# motherboard.net
KiCad netlist of a schematic drawn in EAGLE
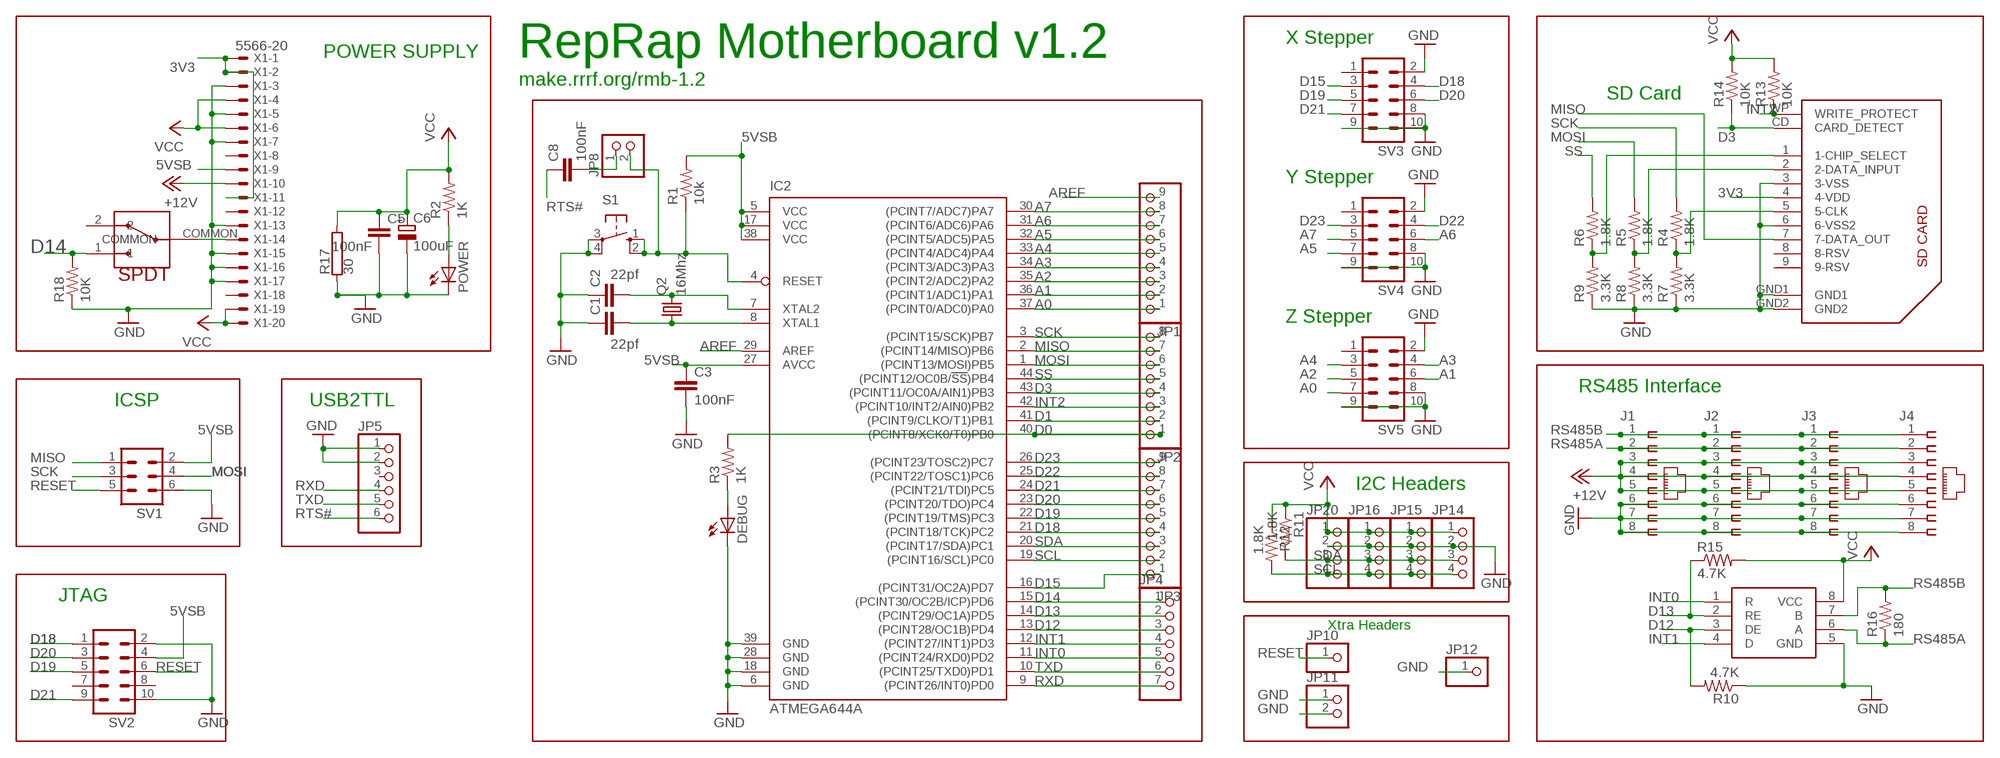
[diagram p0: schematic, sheet 1]

(export (version "E")
  (design (tool "Eeschema 10.0.6"))
  (components
    (comp (ref "C1")
      (value "22pf")
      (footprint "eagle-import:C1206")
      (libsource (lib "eagle-import") (part "C-EUC1206"))
    )
    (comp (ref "C2")
      (value "22pf")
      (footprint "eagle-import:C1206")
      (libsource (lib "eagle-import") (part "C-EUC1206"))
    )
    (comp (ref "C3")
      (value "100nF")
      (footprint "eagle-import:C1206")
      (libsource (lib "eagle-import") (part "C-EUC1206"))
    )
    (comp (ref "C5")
      (value "100nF")
      (footprint "eagle-import:C1206")
      (libsource (lib "eagle-import") (part "C-EUC1206"))
    )
    (comp (ref "C6")
      (value "100uF")
      (footprint "eagle-import:SANYO-OSCON_SMD_B6")
      (libsource (lib "eagle-import") (part "CPOL-EUSANYO_SMD_B6"))
    )
    (comp (ref "C8")
      (value "100nF")
      (footprint "eagle-import:C1206")
      (libsource (lib "eagle-import") (part "C-EUC1206"))
    )
    (comp (ref "DEBUG")
      (value "LEDCHIPLED_1206")
      (footprint "eagle-import:CHIPLED_1206")
      (libsource (lib "eagle-import") (part "LEDCHIPLED_1206"))
    )
    (comp (ref "IC1")
      (value "SN75176ASOIC")
      (footprint "eagle-import:SO08")
      (libsource (lib "eagle-import") (part "SN75176ASOIC"))
    )
    (comp (ref "IC2")
      (value "ATMEGA644A")
      (footprint "eagle-import:TQFP44")
      (libsource (lib "eagle-import") (part "ATMEGA644A"))
    )
    (comp (ref "J1")
      (value "555164-1")
      (footprint "eagle-import:555164-1")
      (libsource (lib "eagle-import") (part "555164-1"))
    )
    (comp (ref "J2")
      (value "555164-1")
      (footprint "eagle-import:555164-1")
      (libsource (lib "eagle-import") (part "555164-1"))
    )
    (comp (ref "J3")
      (value "555164-1")
      (footprint "eagle-import:555164-1")
      (libsource (lib "eagle-import") (part "555164-1"))
    )
    (comp (ref "J4")
      (value "555164-1")
      (footprint "eagle-import:555164-1")
      (libsource (lib "eagle-import") (part "555164-1"))
    )
    (comp (ref "JP1")
      (value "PINHD-1X9")
      (footprint "eagle-import:1X09")
      (libsource (lib "eagle-import") (part "PINHD-1X9"))
    )
    (comp (ref "JP2")
      (value "PINHD-1X8")
      (footprint "eagle-import:1X08")
      (libsource (lib "eagle-import") (part "PINHD-1X8"))
    )
    (comp (ref "JP3")
      (value "PINHD-1X9")
      (footprint "eagle-import:1X09")
      (libsource (lib "eagle-import") (part "PINHD-1X9"))
    )
    (comp (ref "JP4")
      (value "PINHD-1X7")
      (footprint "eagle-import:1X07")
      (libsource (lib "eagle-import") (part "PINHD-1X7"))
    )
    (comp (ref "JP5")
      (value "PINHD-1X6")
      (footprint "eagle-import:1X06")
      (libsource (lib "eagle-import") (part "PINHD-1X6"))
    )
    (comp (ref "JP8")
      (value "PINHD-1X2")
      (footprint "eagle-import:1X02")
      (libsource (lib "eagle-import") (part "PINHD-1X2"))
    )
    (comp (ref "JP10")
      (value "PINHD-1X1")
      (footprint "eagle-import:1X01")
      (libsource (lib "eagle-import") (part "PINHD-1X1"))
    )
    (comp (ref "JP11")
      (value "PINHD-1X2")
      (footprint "eagle-import:1X02")
      (libsource (lib "eagle-import") (part "PINHD-1X2"))
    )
    (comp (ref "JP12")
      (value "PINHD-1X1")
      (footprint "eagle-import:1X01")
      (libsource (lib "eagle-import") (part "PINHD-1X1"))
    )
    (comp (ref "JP14")
      (value "PINHD-1X4")
      (footprint "eagle-import:1X04")
      (libsource (lib "eagle-import") (part "PINHD-1X4"))
    )
    (comp (ref "JP15")
      (value "PINHD-1X4")
      (footprint "eagle-import:1X04")
      (libsource (lib "eagle-import") (part "PINHD-1X4"))
    )
    (comp (ref "JP16")
      (value "PINHD-1X4")
      (footprint "eagle-import:1X04")
      (libsource (lib "eagle-import") (part "PINHD-1X4"))
    )
    (comp (ref "JP20")
      (value "PINHD-1X4")
      (footprint "eagle-import:1X04")
      (libsource (lib "eagle-import") (part "PINHD-1X4"))
    )
    (comp (ref "POWER")
      (value "LEDCHIPLED_1206")
      (footprint "eagle-import:CHIPLED_1206")
      (libsource (lib "eagle-import") (part "LEDCHIPLED_1206"))
    )
    (comp (ref "Q2")
      (value "16Mhz")
      (footprint "eagle-import:HC49U-V")
      (libsource (lib "eagle-import") (part "CRYSTALHC49UV"))
    )
    (comp (ref "R1")
      (value "10k")
      (footprint "eagle-import:R1206")
      (libsource (lib "eagle-import") (part "R-US_R1206"))
    )
    (comp (ref "R2")
      (value "1K")
      (footprint "eagle-import:R1206")
      (libsource (lib "eagle-import") (part "R-US_R1206"))
    )
    (comp (ref "R3")
      (value "1K")
      (footprint "eagle-import:R1206")
      (libsource (lib "eagle-import") (part "resistor_R-US_R1206"))
    )
    (comp (ref "R4")
      (value "1.8K")
      (footprint "eagle-import:R1206")
      (libsource (lib "eagle-import") (part "resistor_R-US_R1206"))
    )
    (comp (ref "R5")
      (value "1.8K")
      (footprint "eagle-import:R1206")
      (libsource (lib "eagle-import") (part "resistor_R-US_R1206"))
    )
    (comp (ref "R6")
      (value "1.8K")
      (footprint "eagle-import:R1206")
      (libsource (lib "eagle-import") (part "resistor_R-US_R1206"))
    )
    (comp (ref "R7")
      (value "3.3K")
      (footprint "eagle-import:R1206")
      (libsource (lib "eagle-import") (part "resistor_R-US_R1206"))
    )
    (comp (ref "R8")
      (value "3.3K")
      (footprint "eagle-import:R1206")
      (libsource (lib "eagle-import") (part "resistor_R-US_R1206"))
    )
    (comp (ref "R9")
      (value "3.3K")
      (footprint "eagle-import:R1206")
      (libsource (lib "eagle-import") (part "resistor_R-US_R1206"))
    )
    (comp (ref "R10")
      (value "4.7K")
      (footprint "eagle-import:R1206")
      (libsource (lib "eagle-import") (part "R-US_R1206"))
    )
    (comp (ref "R11")
      (value "1.8K")
      (footprint "eagle-import:R1206")
      (libsource (lib "eagle-import") (part "R-US_R1206"))
    )
    (comp (ref "R12")
      (value "1.8K")
      (footprint "eagle-import:R1206")
      (libsource (lib "eagle-import") (part "R-US_R1206"))
    )
    (comp (ref "R13")
      (value "10K")
      (footprint "eagle-import:R1206")
      (libsource (lib "eagle-import") (part "R-US_R1206"))
    )
    (comp (ref "R14")
      (value "10K")
      (footprint "eagle-import:R1206")
      (libsource (lib "eagle-import") (part "R-US_R1206"))
    )
    (comp (ref "R15")
      (value "4.7K")
      (footprint "eagle-import:R1206")
      (libsource (lib "eagle-import") (part "R-US_R1206"))
    )
    (comp (ref "R16")
      (value "180")
      (footprint "eagle-import:R1206")
      (libsource (lib "eagle-import") (part "R-US_R1206"))
    )
    (comp (ref "R17")
      (value "30")
      (footprint "eagle-import:KH206-8")
      (libsource (lib "eagle-import") (part "RKH206-8"))
    )
    (comp (ref "R18")
      (value "10K")
      (footprint "eagle-import:R1206")
      (libsource (lib "eagle-import") (part "resistor_R-US_R1206"))
    )
    (comp (ref "S1")
      (value "10-XX")
      (footprint "eagle-import:B3F-10XX")
      (libsource (lib "eagle-import") (part "10-XX"))
    )
    (comp (ref "SV1")
      (value "ML6")
      (footprint "eagle-import:ML6")
      (libsource (lib "eagle-import") (part "ML6"))
    )
    (comp (ref "SV2")
      (value "ML10")
      (footprint "eagle-import:ML10")
      (libsource (lib "eagle-import") (part "ML10"))
    )
    (comp (ref "SV3")
      (value "ML10")
      (footprint "eagle-import:ML10")
      (libsource (lib "eagle-import") (part "ML10"))
    )
    (comp (ref "SV4")
      (value "ML10")
      (footprint "eagle-import:ML10")
      (libsource (lib "eagle-import") (part "con-ml_ML10"))
    )
    (comp (ref "SV5")
      (value "ML10")
      (footprint "eagle-import:ML10")
      (libsource (lib "eagle-import") (part "con-ml_ML10"))
    )
    (comp (ref "U$2")
      (value "SPDT")
      (footprint "eagle-import:10SP001")
      (libsource (lib "eagle-import") (part "SPDT"))
    )
    (comp (ref "U$8")
      (value "SDCARD")
      (footprint "eagle-import:3M-SDCARD")
      (libsource (lib "eagle-import") (part "SDCARD"))
    )
    (comp (ref "X1")
      (value "5566-20")
      (footprint "eagle-import:5566-20")
      (libsource (lib "eagle-import") (part "5566-20"))
    )
  )
  (nets
    (net (code "1") (name "+12V") (class "Default")
      (node (ref "J1") (pin "3") (pinfunction "3_3") (pintype "passive"))
      (node (ref "J1") (pin "4") (pinfunction "4_4") (pintype "passive"))
      (node (ref "J1") (pin "5") (pinfunction "5_5") (pintype "passive"))
      (node (ref "J2") (pin "3") (pinfunction "3_3") (pintype "passive"))
      (node (ref "J2") (pin "4") (pinfunction "4_4") (pintype "passive"))
      (node (ref "J2") (pin "5") (pinfunction "5_5") (pintype "passive"))
      (node (ref "J3") (pin "3") (pinfunction "3_3") (pintype "passive"))
      (node (ref "J3") (pin "4") (pinfunction "4_4") (pintype "passive"))
      (node (ref "J3") (pin "5") (pinfunction "5_5") (pintype "passive"))
      (node (ref "J4") (pin "3") (pinfunction "3_3") (pintype "passive"))
      (node (ref "J4") (pin "4") (pinfunction "4_4") (pintype "passive"))
      (node (ref "J4") (pin "5") (pinfunction "5_5") (pintype "passive"))
      (node (ref "X1") (pin "10") (pinfunction "S_10") (pintype "passive"))
    )
    (net (code "2") (name "/3V3") (class "Default")
      (node (ref "U$8") (pin "4") (pinfunction "4-VDD_4") (pintype "bidirectional"))
      (node (ref "X1") (pin "1") (pinfunction "S_1") (pintype "passive"))
      (node (ref "X1") (pin "11") (pinfunction "S_11") (pintype "passive"))
      (node (ref "X1") (pin "2") (pinfunction "S_2") (pintype "passive"))
    )
    (net (code "3") (name "/5VSB") (class "Default")
      (node (ref "C3") (pin "1") (pinfunction "1_1") (pintype "passive"))
      (node (ref "IC2") (pin "17") (pinfunction "VCC_17") (pintype "power_in"))
      (node (ref "IC2") (pin "27") (pinfunction "AVCC_27") (pintype "power_in"))
      (node (ref "IC2") (pin "38") (pinfunction "VCC_38") (pintype "power_in"))
      (node (ref "IC2") (pin "5") (pinfunction "VCC_5") (pintype "power_in"))
      (node (ref "R1") (pin "2") (pinfunction "2_2") (pintype "passive"))
      (node (ref "SV1") (pin "2") (pinfunction "2_2") (pintype "passive"))
      (node (ref "SV2") (pin "4") (pinfunction "4_4") (pintype "passive"))
      (node (ref "X1") (pin "9") (pinfunction "S_9") (pintype "passive"))
    )
    (net (code "4") (name "/A0") (class "Default")
      (node (ref "IC2") (pin "37") (pinfunction "(PCINT0/ADC0)PA0_37") (pintype "bidirectional"))
      (node (ref "JP1") (pin "1") (pinfunction "1_1") (pintype "passive"))
      (node (ref "SV5") (pin "7") (pinfunction "7_7") (pintype "passive"))
    )
    (net (code "5") (name "/A1") (class "Default")
      (node (ref "IC2") (pin "36") (pinfunction "(PCINT1/ADC1)PA1_36") (pintype "bidirectional"))
      (node (ref "JP1") (pin "2") (pinfunction "2_2") (pintype "passive"))
      (node (ref "SV5") (pin "6") (pinfunction "6_6") (pintype "passive"))
    )
    (net (code "6") (name "/A2") (class "Default")
      (node (ref "IC2") (pin "35") (pinfunction "(PCINT2/ADC2)PA2_35") (pintype "bidirectional"))
      (node (ref "JP1") (pin "3") (pinfunction "3_3") (pintype "passive"))
      (node (ref "SV5") (pin "5") (pinfunction "5_5") (pintype "passive"))
    )
    (net (code "7") (name "/A3") (class "Default")
      (node (ref "IC2") (pin "34") (pinfunction "(PCINT3/ADC3)PA3_34") (pintype "bidirectional"))
      (node (ref "JP1") (pin "4") (pinfunction "4_4") (pintype "passive"))
      (node (ref "SV5") (pin "4") (pinfunction "4_4") (pintype "passive"))
    )
    (net (code "8") (name "/A4") (class "Default")
      (node (ref "IC2") (pin "33") (pinfunction "(PCINT4/ADC4)PA4_33") (pintype "bidirectional"))
      (node (ref "JP1") (pin "5") (pinfunction "5_5") (pintype "passive"))
      (node (ref "SV5") (pin "3") (pinfunction "3_3") (pintype "passive"))
    )
    (net (code "9") (name "/A5") (class "Default")
      (node (ref "IC2") (pin "32") (pinfunction "(PCINT5/ADC5)PA5_32") (pintype "bidirectional"))
      (node (ref "JP1") (pin "6") (pinfunction "6_6") (pintype "passive"))
      (node (ref "SV4") (pin "7") (pinfunction "7_7") (pintype "passive"))
    )
    (net (code "10") (name "/A6") (class "Default")
      (node (ref "IC2") (pin "31") (pinfunction "(PCINT6/ADC6)PA6_31") (pintype "bidirectional"))
      (node (ref "JP1") (pin "7") (pinfunction "7_7") (pintype "passive"))
      (node (ref "SV4") (pin "6") (pinfunction "6_6") (pintype "passive"))
    )
    (net (code "11") (name "/A7") (class "Default")
      (node (ref "IC2") (pin "30") (pinfunction "(PCINT7/ADC7)PA7_30") (pintype "bidirectional"))
      (node (ref "JP1") (pin "8") (pinfunction "8_8") (pintype "passive"))
      (node (ref "SV4") (pin "5") (pinfunction "5_5") (pintype "passive"))
    )
    (net (code "12") (name "/AREF") (class "Default")
      (node (ref "IC2") (pin "29") (pinfunction "AREF_29") (pintype "passive"))
      (node (ref "JP1") (pin "9") (pinfunction "9_9") (pintype "passive"))
    )
    (net (code "13") (name "/D0") (class "Default")
      (node (ref "IC2") (pin "40") (pinfunction "(PCINT8/XCK0/T0)PB0_40") (pintype "bidirectional"))
      (node (ref "JP2") (pin "1") (pinfunction "1_1") (pintype "passive"))
      (node (ref "R3") (pin "2") (pinfunction "2_2") (pintype "passive"))
    )
    (net (code "14") (name "/D1") (class "Default")
      (node (ref "IC2") (pin "41") (pinfunction "(PCINT9/CLKO/T1)PB1_41") (pintype "bidirectional"))
      (node (ref "JP2") (pin "2") (pinfunction "2_2") (pintype "passive"))
    )
    (net (code "15") (name "/D3") (class "Default")
      (node (ref "IC2") (pin "43") (pinfunction "(PCINT11/OC0A/AIN1)PB3_43") (pintype "bidirectional"))
      (node (ref "JP2") (pin "4") (pinfunction "4_4") (pintype "passive"))
      (node (ref "R14") (pin "1") (pinfunction "1_1") (pintype "passive"))
      (node (ref "U$8") (pin "CD") (pinfunction "CARD_DETECT_CD") (pintype "bidirectional"))
    )
    (net (code "16") (name "/D12") (class "Default")
      (node (ref "IC1") (pin "3") (pinfunction "DE_3") (pintype "bidirectional"))
      (node (ref "IC2") (pin "13") (pinfunction "(PCINT28/OC1B)PD4_13") (pintype "bidirectional"))
      (node (ref "JP4") (pin "3") (pinfunction "3_3") (pintype "passive"))
      (node (ref "R10") (pin "2") (pinfunction "2_2") (pintype "passive"))
    )
    (net (code "17") (name "/D13") (class "Default")
      (node (ref "IC1") (pin "2") (pinfunction "RE_2") (pintype "bidirectional"))
      (node (ref "IC2") (pin "14") (pinfunction "(PCINT29/OC1A)PD5_14") (pintype "bidirectional"))
      (node (ref "JP4") (pin "2") (pinfunction "2_2") (pintype "passive"))
      (node (ref "R15") (pin "1") (pinfunction "1_1") (pintype "passive"))
    )
    (net (code "18") (name "/D14") (class "Default")
      (node (ref "IC2") (pin "15") (pinfunction "(PCINT30/OC2B/ICP)PD6_15") (pintype "bidirectional"))
      (node (ref "JP4") (pin "1") (pinfunction "1_1") (pintype "passive"))
      (node (ref "R18") (pin "2") (pinfunction "2_2") (pintype "passive"))
      (node (ref "U$2") (pin "1") (pinfunction "1_1") (pintype "bidirectional"))
    )
    (net (code "19") (name "/D15") (class "Default")
      (node (ref "IC2") (pin "16") (pinfunction "(PCINT31/OC2A)PD7_16") (pintype "bidirectional"))
      (node (ref "JP3") (pin "1") (pinfunction "1_1") (pintype "passive"))
      (node (ref "SV3") (pin "3") (pinfunction "3_3") (pintype "passive"))
    )
    (net (code "20") (name "/D18") (class "Default")
      (node (ref "IC2") (pin "21") (pinfunction "(PCINT18/TCK)PC2_21") (pintype "output"))
      (node (ref "JP3") (pin "4") (pinfunction "4_4") (pintype "passive"))
      (node (ref "SV2") (pin "1") (pinfunction "1_1") (pintype "passive"))
      (node (ref "SV3") (pin "4") (pinfunction "4_4") (pintype "passive"))
    )
    (net (code "21") (name "/D19") (class "Default")
      (node (ref "IC2") (pin "22") (pinfunction "(PCINT19/TMS)PC3_22") (pintype "output"))
      (node (ref "JP3") (pin "5") (pinfunction "5_5") (pintype "passive"))
      (node (ref "SV2") (pin "5") (pinfunction "5_5") (pintype "passive"))
      (node (ref "SV3") (pin "5") (pinfunction "5_5") (pintype "passive"))
    )
    (net (code "22") (name "/D20") (class "Default")
      (node (ref "IC2") (pin "23") (pinfunction "(PCINT20/TDO)PC4_23") (pintype "output"))
      (node (ref "JP3") (pin "6") (pinfunction "6_6") (pintype "passive"))
      (node (ref "SV2") (pin "3") (pinfunction "3_3") (pintype "passive"))
      (node (ref "SV3") (pin "6") (pinfunction "6_6") (pintype "passive"))
    )
    (net (code "23") (name "/D21") (class "Default")
      (node (ref "IC2") (pin "24") (pinfunction "(PCINT21/TDI)PC5_24") (pintype "output"))
      (node (ref "JP3") (pin "7") (pinfunction "7_7") (pintype "passive"))
      (node (ref "SV2") (pin "9") (pinfunction "9_9") (pintype "passive"))
      (node (ref "SV3") (pin "7") (pinfunction "7_7") (pintype "passive"))
    )
    (net (code "24") (name "/D22") (class "Default")
      (node (ref "IC2") (pin "25") (pinfunction "(PCINT22/TOSC1)PC6_25") (pintype "output"))
      (node (ref "JP3") (pin "8") (pinfunction "8_8") (pintype "passive"))
      (node (ref "SV4") (pin "4") (pinfunction "4_4") (pintype "passive"))
    )
    (net (code "25") (name "/D23") (class "Default")
      (node (ref "IC2") (pin "26") (pinfunction "(PCINT23/TOSC2)PC7_26") (pintype "output"))
      (node (ref "JP3") (pin "9") (pinfunction "9_9") (pintype "passive"))
      (node (ref "SV4") (pin "3") (pinfunction "3_3") (pintype "passive"))
    )
    (net (code "26") (name "/INT0") (class "Default")
      (node (ref "IC1") (pin "1") (pinfunction "R_1") (pintype "bidirectional"))
      (node (ref "IC2") (pin "11") (pinfunction "(PCINT24/RXD0)PD2_11") (pintype "bidirectional"))
      (node (ref "JP4") (pin "5") (pinfunction "5_5") (pintype "passive"))
    )
    (net (code "27") (name "/INT1") (class "Default")
      (node (ref "IC1") (pin "4") (pinfunction "D_4") (pintype "bidirectional"))
      (node (ref "IC2") (pin "12") (pinfunction "(PCINT27/INT1)PD3_12") (pintype "bidirectional"))
      (node (ref "JP4") (pin "4") (pinfunction "4_4") (pintype "passive"))
    )
    (net (code "28") (name "/INT2") (class "Default")
      (node (ref "IC2") (pin "42") (pinfunction "(PCINT10/INT2/AIN0)PB2_42") (pintype "bidirectional"))
      (node (ref "JP2") (pin "3") (pinfunction "3_3") (pintype "passive"))
      (node (ref "R13") (pin "1") (pinfunction "1_1") (pintype "passive"))
      (node (ref "U$8") (pin "WP") (pinfunction "WRITE_PROTECT_WP") (pintype "bidirectional"))
    )
    (net (code "29") (name "/MISO") (class "Default")
      (node (ref "IC2") (pin "2") (pinfunction "(PCINT14/MISO)PB6_2") (pintype "bidirectional"))
      (node (ref "JP2") (pin "7") (pinfunction "7_7") (pintype "passive"))
      (node (ref "SV1") (pin "1") (pinfunction "1_1") (pintype "passive"))
      (node (ref "U$8") (pin "7") (pinfunction "7-DATA_OUT_7") (pintype "bidirectional"))
    )
    (net (code "30") (name "/MOSI") (class "Default")
      (node (ref "IC2") (pin "1") (pinfunction "(PCINT13/MOSI)PB5_1") (pintype "bidirectional"))
      (node (ref "JP2") (pin "6") (pinfunction "6_6") (pintype "passive"))
      (node (ref "R5") (pin "2") (pinfunction "2_2") (pintype "passive"))
      (node (ref "SV1") (pin "4") (pinfunction "4_4") (pintype "passive"))
    )
    (net (code "31") (name "/RESET") (class "Default")
      (node (ref "IC2") (pin "4") (pinfunction "RESET_4") (pintype "input"))
      (node (ref "JP10") (pin "1") (pinfunction "1_1") (pintype "passive"))
      (node (ref "JP8") (pin "2") (pinfunction "2_2") (pintype "passive"))
      (node (ref "R1") (pin "1") (pinfunction "1_1") (pintype "passive"))
      (node (ref "S1") (pin "1") (pinfunction "S_1") (pintype "passive"))
      (node (ref "S1") (pin "2") (pinfunction "S1_2") (pintype "passive"))
      (node (ref "SV1") (pin "5") (pinfunction "5_5") (pintype "passive"))
      (node (ref "SV2") (pin "6") (pinfunction "6_6") (pintype "passive"))
    )
    (net (code "32") (name "/RS485A") (class "Default")
      (node (ref "IC1") (pin "6") (pinfunction "A_6") (pintype "bidirectional"))
      (node (ref "J1") (pin "2") (pinfunction "2_2") (pintype "passive"))
      (node (ref "J2") (pin "2") (pinfunction "2_2") (pintype "passive"))
      (node (ref "J3") (pin "2") (pinfunction "2_2") (pintype "passive"))
      (node (ref "J4") (pin "2") (pinfunction "2_2") (pintype "passive"))
      (node (ref "R16") (pin "1") (pinfunction "1_1") (pintype "passive"))
    )
    (net (code "33") (name "/RS485B") (class "Default")
      (node (ref "IC1") (pin "7") (pinfunction "B_7") (pintype "bidirectional"))
      (node (ref "J1") (pin "1") (pinfunction "1_1") (pintype "passive"))
      (node (ref "J2") (pin "1") (pinfunction "1_1") (pintype "passive"))
      (node (ref "J3") (pin "1") (pinfunction "1_1") (pintype "passive"))
      (node (ref "J4") (pin "1") (pinfunction "1_1") (pintype "passive"))
      (node (ref "R16") (pin "2") (pinfunction "2_2") (pintype "passive"))
    )
    (net (code "34") (name "/RTS#") (class "Default")
      (node (ref "C8") (pin "1") (pinfunction "1_1") (pintype "passive"))
      (node (ref "JP5") (pin "6") (pinfunction "6_6") (pintype "passive"))
    )
    (net (code "35") (name "/RXD") (class "Default")
      (node (ref "IC2") (pin "9") (pinfunction "(PCINT26/INT0)PD0_9") (pintype "bidirectional"))
      (node (ref "JP4") (pin "7") (pinfunction "7_7") (pintype "passive"))
      (node (ref "JP5") (pin "4") (pinfunction "4_4") (pintype "passive"))
    )
    (net (code "36") (name "/SCK") (class "Default")
      (node (ref "IC2") (pin "3") (pinfunction "(PCINT15/SCK)PB7_3") (pintype "bidirectional"))
      (node (ref "JP2") (pin "8") (pinfunction "8_8") (pintype "passive"))
      (node (ref "R4") (pin "2") (pinfunction "2_2") (pintype "passive"))
      (node (ref "SV1") (pin "3") (pinfunction "3_3") (pintype "passive"))
    )
    (net (code "37") (name "/SCL") (class "Default")
      (node (ref "IC2") (pin "19") (pinfunction "(PCINT16/SCL)PC0_19") (pintype "output"))
      (node (ref "JP14") (pin "4") (pinfunction "4_4") (pintype "passive"))
      (node (ref "JP15") (pin "4") (pinfunction "4_4") (pintype "passive"))
      (node (ref "JP16") (pin "4") (pinfunction "4_4") (pintype "passive"))
      (node (ref "JP20") (pin "4") (pinfunction "4_4") (pintype "passive"))
      (node (ref "JP3") (pin "2") (pinfunction "2_2") (pintype "passive"))
      (node (ref "R12") (pin "2") (pinfunction "2_2") (pintype "passive"))
    )
    (net (code "38") (name "/SDA") (class "Default")
      (node (ref "IC2") (pin "20") (pinfunction "(PCINT17/SDA)PC1_20") (pintype "output"))
      (node (ref "JP14") (pin "3") (pinfunction "3_3") (pintype "passive"))
      (node (ref "JP15") (pin "3") (pinfunction "3_3") (pintype "passive"))
      (node (ref "JP16") (pin "3") (pinfunction "3_3") (pintype "passive"))
      (node (ref "JP20") (pin "3") (pinfunction "3_3") (pintype "passive"))
      (node (ref "JP3") (pin "3") (pinfunction "3_3") (pintype "passive"))
      (node (ref "R11") (pin "2") (pinfunction "2_2") (pintype "passive"))
    )
    (net (code "39") (name "/SS") (class "Default")
      (node (ref "IC2") (pin "44") (pinfunction "(PCINT12/OC0B/~{SS})PB4_44") (pintype "bidirectional"))
      (node (ref "JP2") (pin "5") (pinfunction "5_5") (pintype "passive"))
      (node (ref "R6") (pin "2") (pinfunction "2_2") (pintype "passive"))
    )
    (net (code "40") (name "/TXD") (class "Default")
      (node (ref "IC2") (pin "10") (pinfunction "(PCINT25/TXD0)PD1_10") (pintype "bidirectional"))
      (node (ref "JP4") (pin "6") (pinfunction "6_6") (pintype "passive"))
      (node (ref "JP5") (pin "5") (pinfunction "5_5") (pintype "passive"))
    )
    (net (code "41") (name "GND") (class "Default")
      (node (ref "C1") (pin "1") (pinfunction "1_1") (pintype "passive"))
      (node (ref "C2") (pin "1") (pinfunction "1_1") (pintype "passive"))
      (node (ref "C3") (pin "2") (pinfunction "2_2") (pintype "passive"))
      (node (ref "C5") (pin "2") (pinfunction "2_2") (pintype "passive"))
      (node (ref "C6") (pin "-") (pinfunction "-_-") (pintype "passive"))
      (node (ref "DEBUG") (pin "C") (pinfunction "C_C") (pintype "passive"))
      (node (ref "IC1") (pin "5") (pinfunction "GND_5") (pintype "bidirectional"))
      (node (ref "IC2") (pin "18") (pinfunction "GND_18") (pintype "power_in"))
      (node (ref "IC2") (pin "28") (pinfunction "GND_28") (pintype "power_in"))
      (node (ref "IC2") (pin "39") (pinfunction "GND_39") (pintype "power_in"))
      (node (ref "IC2") (pin "6") (pinfunction "GND_6") (pintype "power_in"))
      (node (ref "J1") (pin "6") (pinfunction "6_6") (pintype "passive"))
      (node (ref "J1") (pin "7") (pinfunction "7_7") (pintype "passive"))
      (node (ref "J1") (pin "8") (pinfunction "8_8") (pintype "passive"))
      (node (ref "J2") (pin "6") (pinfunction "6_6") (pintype "passive"))
      (node (ref "J2") (pin "7") (pinfunction "7_7") (pintype "passive"))
      (node (ref "J2") (pin "8") (pinfunction "8_8") (pintype "passive"))
      (node (ref "J3") (pin "6") (pinfunction "6_6") (pintype "passive"))
      (node (ref "J3") (pin "7") (pinfunction "7_7") (pintype "passive"))
      (node (ref "J3") (pin "8") (pinfunction "8_8") (pintype "passive"))
      (node (ref "J4") (pin "6") (pinfunction "6_6") (pintype "passive"))
      (node (ref "J4") (pin "7") (pinfunction "7_7") (pintype "passive"))
      (node (ref "J4") (pin "8") (pinfunction "8_8") (pintype "passive"))
      (node (ref "JP11") (pin "1") (pinfunction "1_1") (pintype "passive"))
      (node (ref "JP11") (pin "2") (pinfunction "2_2") (pintype "passive"))
      (node (ref "JP12") (pin "1") (pinfunction "1_1") (pintype "passive"))
      (node (ref "JP14") (pin "2") (pinfunction "2_2") (pintype "passive"))
      (node (ref "JP15") (pin "2") (pinfunction "2_2") (pintype "passive"))
      (node (ref "JP16") (pin "2") (pinfunction "2_2") (pintype "passive"))
      (node (ref "JP20") (pin "2") (pinfunction "2_2") (pintype "passive"))
      (node (ref "JP5") (pin "1") (pinfunction "1_1") (pintype "passive"))
      (node (ref "JP5") (pin "2") (pinfunction "2_2") (pintype "passive"))
      (node (ref "POWER") (pin "C") (pinfunction "C_C") (pintype "passive"))
      (node (ref "R10") (pin "1") (pinfunction "1_1") (pintype "passive"))
      (node (ref "R17") (pin "1") (pinfunction "1_1") (pintype "passive"))
      (node (ref "R18") (pin "1") (pinfunction "1_1") (pintype "passive"))
      (node (ref "R7") (pin "1") (pinfunction "1_1") (pintype "passive"))
      (node (ref "R8") (pin "1") (pinfunction "1_1") (pintype "passive"))
      (node (ref "R9") (pin "1") (pinfunction "1_1") (pintype "passive"))
      (node (ref "S1") (pin "3") (pinfunction "P_3") (pintype "passive"))
      (node (ref "S1") (pin "4") (pinfunction "P1_4") (pintype "passive"))
      (node (ref "SV1") (pin "6") (pinfunction "6_6") (pintype "passive"))
      (node (ref "SV2") (pin "10") (pinfunction "10_10") (pintype "passive"))
      (node (ref "SV2") (pin "2") (pinfunction "2_2") (pintype "passive"))
      (node (ref "SV3") (pin "10") (pinfunction "10_10") (pintype "passive"))
      (node (ref "SV3") (pin "2") (pinfunction "2_2") (pintype "passive"))
      (node (ref "SV3") (pin "8") (pinfunction "8_8") (pintype "passive"))
      (node (ref "SV3") (pin "9") (pinfunction "9_9") (pintype "passive"))
      (node (ref "SV4") (pin "10") (pinfunction "10_10") (pintype "passive"))
      (node (ref "SV4") (pin "2") (pinfunction "2_2") (pintype "passive"))
      (node (ref "SV4") (pin "8") (pinfunction "8_8") (pintype "passive"))
      (node (ref "SV4") (pin "9") (pinfunction "9_9") (pintype "passive"))
      (node (ref "SV5") (pin "10") (pinfunction "10_10") (pintype "passive"))
      (node (ref "SV5") (pin "2") (pinfunction "2_2") (pintype "passive"))
      (node (ref "SV5") (pin "8") (pinfunction "8_8") (pintype "passive"))
      (node (ref "SV5") (pin "9") (pinfunction "9_9") (pintype "passive"))
      (node (ref "U$8") (pin "3") (pinfunction "3-VSS_3") (pintype "bidirectional"))
      (node (ref "U$8") (pin "6") (pinfunction "6-VSS2_6") (pintype "bidirectional"))
      (node (ref "U$8") (pin "GND1") (pinfunction "GND1_GND1") (pintype "bidirectional"))
      (node (ref "U$8") (pin "GND2") (pinfunction "GND2_GND2") (pintype "bidirectional"))
      (node (ref "X1") (pin "13") (pinfunction "S_13") (pintype "passive"))
      (node (ref "X1") (pin "15") (pinfunction "S_15") (pintype "passive"))
      (node (ref "X1") (pin "16") (pinfunction "S_16") (pintype "passive"))
      (node (ref "X1") (pin "17") (pinfunction "S_17") (pintype "passive"))
      (node (ref "X1") (pin "3") (pinfunction "S_3") (pintype "passive"))
      (node (ref "X1") (pin "5") (pinfunction "S_5") (pintype "passive"))
      (node (ref "X1") (pin "7") (pinfunction "S_7") (pintype "passive"))
    )
    (net (code "42") (name "Net-(C8-Pad2)") (class "Default")
      (node (ref "C8") (pin "2") (pinfunction "2_2") (pintype "passive"))
      (node (ref "JP8") (pin "1") (pinfunction "1_1") (pintype "passive"))
    )
    (net (code "43") (name "Net-(DEBUG-PadA)") (class "Default")
      (node (ref "DEBUG") (pin "A") (pinfunction "A_A") (pintype "passive"))
      (node (ref "R3") (pin "1") (pinfunction "1_1") (pintype "passive"))
    )
    (net (code "44") (name "Net-(IC2-XTAL1)") (class "Default")
      (node (ref "C1") (pin "2") (pinfunction "2_2") (pintype "passive"))
      (node (ref "IC2") (pin "8") (pinfunction "XTAL1_8") (pintype "bidirectional"))
      (node (ref "Q2") (pin "1") (pinfunction "1_1") (pintype "passive"))
    )
    (net (code "45") (name "Net-(IC2-XTAL2)") (class "Default")
      (node (ref "C2") (pin "2") (pinfunction "2_2") (pintype "passive"))
      (node (ref "IC2") (pin "7") (pinfunction "XTAL2_7") (pintype "bidirectional"))
      (node (ref "Q2") (pin "2") (pinfunction "2_2") (pintype "passive"))
    )
    (net (code "46") (name "Net-(POWER-PadA)") (class "Default")
      (node (ref "POWER") (pin "A") (pinfunction "A_A") (pintype "passive"))
      (node (ref "R2") (pin "1") (pinfunction "1_1") (pintype "passive"))
    )
    (net (code "47") (name "Net-(U$8-1-CHIP_SELECT)") (class "Default")
      (node (ref "R6") (pin "1") (pinfunction "1_1") (pintype "passive"))
      (node (ref "R9") (pin "2") (pinfunction "2_2") (pintype "passive"))
      (node (ref "U$8") (pin "1") (pinfunction "1-CHIP_SELECT_1") (pintype "bidirectional"))
    )
    (net (code "48") (name "Net-(U$8-2-DATA_INPUT)") (class "Default")
      (node (ref "R5") (pin "1") (pinfunction "1_1") (pintype "passive"))
      (node (ref "R8") (pin "2") (pinfunction "2_2") (pintype "passive"))
      (node (ref "U$8") (pin "2") (pinfunction "2-DATA_INPUT_2") (pintype "bidirectional"))
    )
    (net (code "49") (name "Net-(U$8-5-CLK)") (class "Default")
      (node (ref "R4") (pin "1") (pinfunction "1_1") (pintype "passive"))
      (node (ref "R7") (pin "2") (pinfunction "2_2") (pintype "passive"))
      (node (ref "U$8") (pin "5") (pinfunction "5-CLK_5") (pintype "bidirectional"))
    )
    (net (code "50") (name "Net-(X1F-S)") (class "Default")
      (node (ref "U$2") (pin "COMMON") (pinfunction "COMMON_COMMON") (pintype "bidirectional"))
      (node (ref "X1") (pin "14") (pinfunction "S_14") (pintype "passive"))
    )
    (net (code "51") (name "VCC") (class "Default")
      (node (ref "C5") (pin "1") (pinfunction "1_1") (pintype "passive"))
      (node (ref "C6") (pin "+") (pinfunction "+_+") (pintype "passive"))
      (node (ref "IC1") (pin "8") (pinfunction "VCC_8") (pintype "bidirectional"))
      (node (ref "JP14") (pin "1") (pinfunction "1_1") (pintype "passive"))
      (node (ref "JP15") (pin "1") (pinfunction "1_1") (pintype "passive"))
      (node (ref "JP16") (pin "1") (pinfunction "1_1") (pintype "passive"))
      (node (ref "JP20") (pin "1") (pinfunction "1_1") (pintype "passive"))
      (node (ref "R11") (pin "1") (pinfunction "1_1") (pintype "passive"))
      (node (ref "R12") (pin "1") (pinfunction "1_1") (pintype "passive"))
      (node (ref "R13") (pin "2") (pinfunction "2_2") (pintype "passive"))
      (node (ref "R14") (pin "2") (pinfunction "2_2") (pintype "passive"))
      (node (ref "R15") (pin "2") (pinfunction "2_2") (pintype "passive"))
      (node (ref "R17") (pin "2") (pinfunction "2_2") (pintype "passive"))
      (node (ref "R2") (pin "2") (pinfunction "2_2") (pintype "passive"))
      (node (ref "X1") (pin "19") (pinfunction "S_19") (pintype "passive"))
      (node (ref "X1") (pin "20") (pinfunction "S_20") (pintype "passive"))
      (node (ref "X1") (pin "4") (pinfunction "S_4") (pintype "passive"))
      (node (ref "X1") (pin "6") (pinfunction "S_6") (pintype "passive"))
    )
    (net (code "52") (name "unconnected-(JP5-Pad3)") (class "Default")
      (node (ref "JP5") (pin "3") (pinfunction "3_3") (pintype "passive"))
    )
    (net (code "53") (name "unconnected-(SV2-Pad7)") (class "Default")
      (node (ref "SV2") (pin "7") (pinfunction "7_7") (pintype "passive"))
    )
    (net (code "54") (name "unconnected-(SV2-Pad8)") (class "Default")
      (node (ref "SV2") (pin "8") (pinfunction "8_8") (pintype "passive"))
    )
    (net (code "55") (name "unconnected-(SV3-Pad1)") (class "Default")
      (node (ref "SV3") (pin "1") (pinfunction "1_1") (pintype "passive"))
    )
    (net (code "56") (name "unconnected-(SV4-Pad1)") (class "Default")
      (node (ref "SV4") (pin "1") (pinfunction "1_1") (pintype "passive"))
    )
    (net (code "57") (name "unconnected-(SV5-Pad1)") (class "Default")
      (node (ref "SV5") (pin "1") (pinfunction "1_1") (pintype "passive"))
    )
    (net (code "58") (name "unconnected-(U$2-Pad2)") (class "Default")
      (node (ref "U$2") (pin "2") (pinfunction "2_2") (pintype "bidirectional"))
    )
    (net (code "59") (name "unconnected-(U$8-8-RSV-Pad8)") (class "Default")
      (node (ref "U$8") (pin "8") (pinfunction "8-RSV_8") (pintype "bidirectional"))
    )
    (net (code "60") (name "unconnected-(U$8-9-RSV-Pad9)") (class "Default")
      (node (ref "U$8") (pin "9") (pinfunction "9-RSV_9") (pintype "bidirectional"))
    )
    (net (code "61") (name "unconnected-(X1D-S-Pad12)") (class "Default")
      (node (ref "X1") (pin "12") (pinfunction "S_12") (pintype "passive"))
    )
    (net (code "62") (name "unconnected-(X1J-S-Pad18)") (class "Default")
      (node (ref "X1") (pin "18") (pinfunction "S_18") (pintype "passive"))
    )
    (net (code "63") (name "unconnected-(X1S-S-Pad8)") (class "Default")
      (node (ref "X1") (pin "8") (pinfunction "S_8") (pintype "passive"))
    )
  )
)
